# VestibularVR_H1-module_v1_0.net
KiCad netlist of a schematic drawn in EAGLE
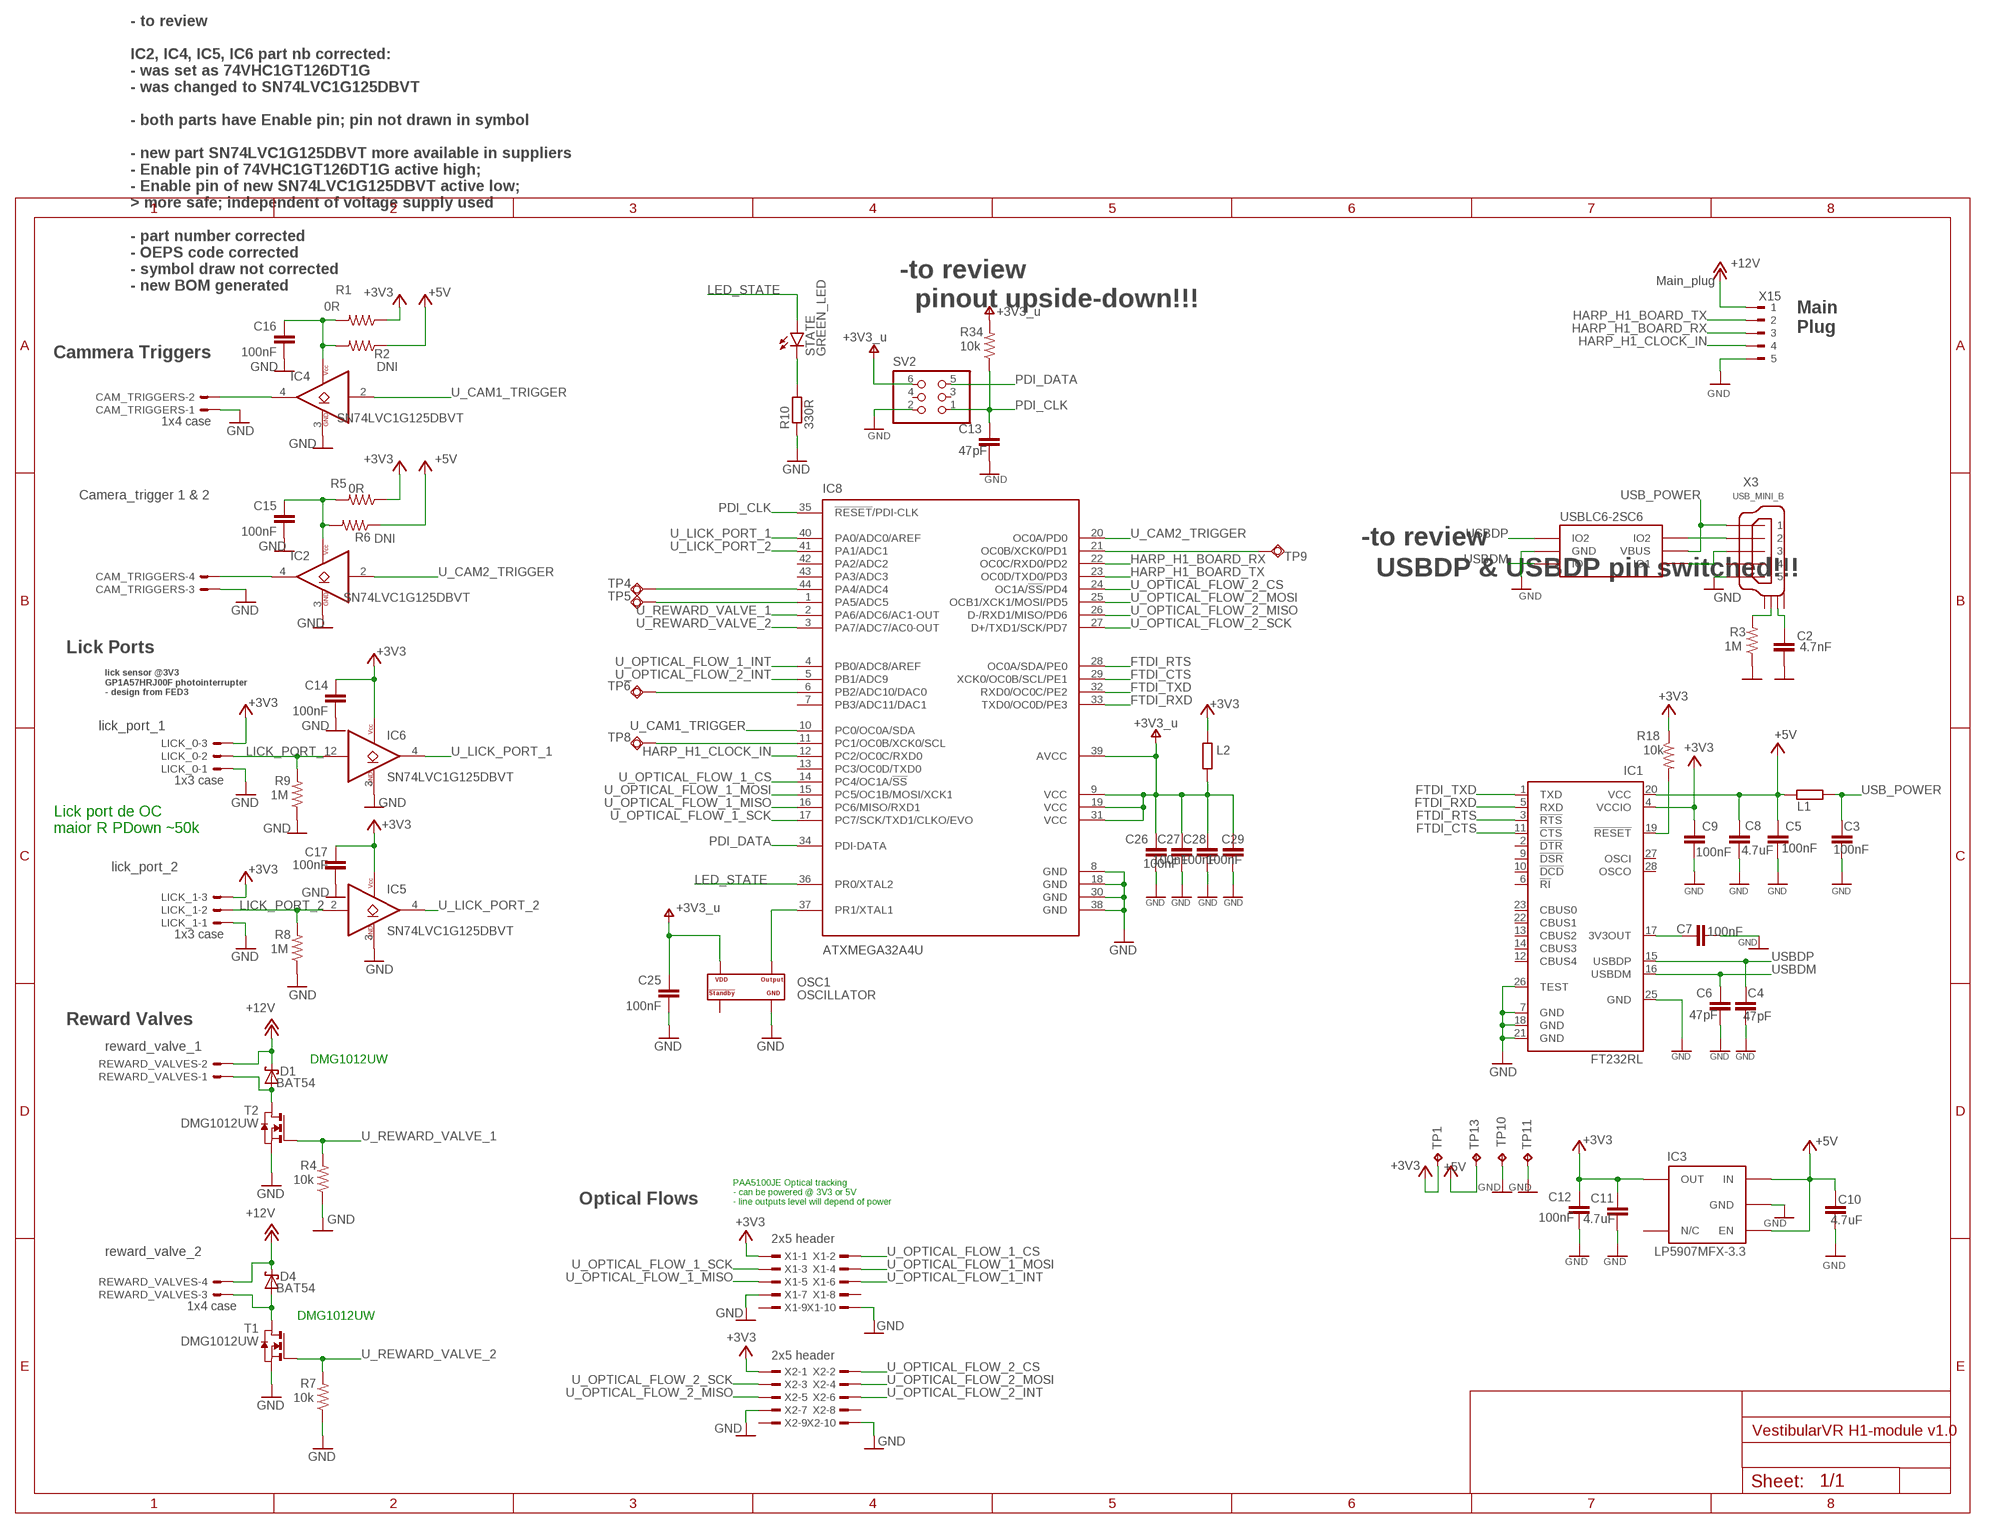
[diagram p0: schematic, sheet 1]

(export (version "E")
  (design (tool "Eeschema 10.0.6"))
  (components
    (comp (ref "C2")
      (value "4.7nF")
      (footprint "eagle-import:C0402K")
      (fields (field (name "MPN") "CC0402KRX7R8BB472"))
      (libsource (lib "eagle-import") (part "C-EUC0402K"))
    )
    (comp (ref "C3")
      (value "100nF")
      (footprint "eagle-import:C0402K")
      (fields (field (name "MPN") "C1005X7R1H104K050BB"))
      (libsource (lib "eagle-import") (part "C-EUC0402K"))
    )
    (comp (ref "C4")
      (value "47pF")
      (footprint "eagle-import:C0402K")
      (fields (field (name "MPN") "04025A470JAT2A"))
      (libsource (lib "eagle-import") (part "C-EUC0402K"))
    )
    (comp (ref "C5")
      (value "100nF")
      (footprint "eagle-import:C0402K")
      (fields (field (name "MPN") "C1005X7R1H104K050BB"))
      (libsource (lib "eagle-import") (part "C-EUC0402K"))
    )
    (comp (ref "C6")
      (value "47pF")
      (footprint "eagle-import:C0402K")
      (fields (field (name "MPN") "04025A470JAT2A"))
      (libsource (lib "eagle-import") (part "C-EUC0402K"))
    )
    (comp (ref "C7")
      (value "100nF")
      (footprint "eagle-import:C0402K")
      (fields (field (name "MPN") "C1005X7R1H104K050BB"))
      (libsource (lib "eagle-import") (part "C-EUC0402K"))
    )
    (comp (ref "C8")
      (value "4.7uF")
      (footprint "eagle-import:C0603")
      (fields (field (name "MPN") "C1608X6S1C475K080AC"))
      (libsource (lib "eagle-import") (part "C-EUC0603"))
    )
    (comp (ref "C9")
      (value "100nF")
      (footprint "eagle-import:C0402K")
      (fields (field (name "MPN") "C1005X7R1H104K050BB"))
      (libsource (lib "eagle-import") (part "C-EUC0402K"))
    )
    (comp (ref "C10")
      (value "4.7uF")
      (footprint "eagle-import:C0603K")
      (fields (field (name "MPN") "C1608X6S1C475K080AC"))
      (libsource (lib "eagle-import") (part "C-EUC0603K"))
    )
    (comp (ref "C11")
      (value "4.7uF")
      (footprint "eagle-import:C0603K")
      (fields (field (name "MPN") "C1608X6S1C475K080AC"))
      (libsource (lib "eagle-import") (part "C-EUC0603K"))
    )
    (comp (ref "C12")
      (value "100nF")
      (footprint "eagle-import:C0402K")
      (fields (field (name "MPN") "C1005X7R1H104K050BB"))
      (libsource (lib "eagle-import") (part "C-EUC0402K"))
    )
    (comp (ref "C13")
      (value "47pF")
      (footprint "eagle-import:C0402K")
      (fields (field (name "MPN") "04025A470JAT2A"))
      (libsource (lib "eagle-import") (part "C-EUC0402K"))
    )
    (comp (ref "C14")
      (value "100nF")
      (footprint "eagle-import:C0402K")
      (fields (field (name "MPN") "C1005X7R1H104K050BB"))
      (libsource (lib "eagle-import") (part "C-EUC0402K"))
    )
    (comp (ref "C15")
      (value "100nF")
      (footprint "eagle-import:C0402K")
      (fields (field (name "MPN") "C1005X7R1H104K050BB"))
      (libsource (lib "eagle-import") (part "C-EUC0402K"))
    )
    (comp (ref "C16")
      (value "100nF")
      (footprint "eagle-import:C0402K")
      (fields (field (name "MPN") "C1005X7R1H104K050BB"))
      (libsource (lib "eagle-import") (part "C-EUC0402K"))
    )
    (comp (ref "C17")
      (value "100nF")
      (footprint "eagle-import:C0402K")
      (fields (field (name "MPN") "C1005X7R1H104K050BB"))
      (libsource (lib "eagle-import") (part "C-EUC0402K"))
    )
    (comp (ref "C25")
      (value "100nF")
      (footprint "eagle-import:C0402K")
      (fields (field (name "MPN") "C1005X7R1H104K050BB"))
      (libsource (lib "eagle-import") (part "C-EUC0402K"))
    )
    (comp (ref "C26")
      (value "100nF")
      (footprint "eagle-import:C0402K")
      (fields (field (name "MPN") "C1005X7R1H104K050BB"))
      (libsource (lib "eagle-import") (part "C-EUC0402K"))
    )
    (comp (ref "C27")
      (value "100nF")
      (footprint "eagle-import:C0402K")
      (fields (field (name "MPN") "C1005X7R1H104K050BB"))
      (libsource (lib "eagle-import") (part "C-EUC0402K"))
    )
    (comp (ref "C28")
      (value "100nF")
      (footprint "eagle-import:C0402K")
      (fields (field (name "MPN") "C1005X7R1H104K050BB"))
      (libsource (lib "eagle-import") (part "C-EUC0402K"))
    )
    (comp (ref "C29")
      (value "100nF")
      (footprint "eagle-import:C0402K")
      (fields (field (name "MPN") "C1005X7R1H104K050BB"))
      (libsource (lib "eagle-import") (part "C-EUC0402K"))
    )
    (comp (ref "CAM_TRIGGERS")
      (value "1x4 case")
      (footprint "eagle-import:22-23-2041")
      (fields
        (field (name "MF") "MOLEX")
        (field (name "MPN") "22-23-2041")
        (field (name "MF_1") "-")
        (field (name "MPN_1") "282834-4")
        (field (name "OEPS") "OEPS070036")
      )
      (libsource (lib "eagle-import") (part "22-23-2041"))
    )
    (comp (ref "D1")
      (value "BAT54")
      (footprint "eagle-import:SOT23")
      (fields (field (name "MPN") "BAT54SLT1G"))
      (libsource (lib "eagle-import") (part "BAT54"))
    )
    (comp (ref "D4")
      (value "BAT54")
      (footprint "eagle-import:SOT23")
      (fields (field (name "MPN") "BAT54SLT1G"))
      (libsource (lib "eagle-import") (part "BAT54"))
    )
    (comp (ref "IC1")
      (value "FT232RL")
      (footprint "eagle-import:SSOP28")
      (libsource (lib "eagle-import") (part "FT232RL"))
    )
    (comp (ref "IC2")
      (value "SN74LVC1G125DBVT")
      (footprint "eagle-import:SOT23-5")
      (libsource (lib "eagle-import") (part "74LVC1G07DBV"))
    )
    (comp (ref "IC3")
      (value "LP5907MFX-3.3")
      (footprint "eagle-import:TSOT23-5")
      (fields (field (name "MPN") "LP5907MFX-3.3/NOPB"))
      (libsource (lib "eagle-import") (part "TLV700XX"))
    )
    (comp (ref "IC4")
      (value "SN74LVC1G125DBVT")
      (footprint "eagle-import:SOT23-5")
      (libsource (lib "eagle-import") (part "74LVC1G07DBV"))
    )
    (comp (ref "IC5")
      (value "SN74LVC1G125DBVT")
      (footprint "eagle-import:SOT23-5")
      (libsource (lib "eagle-import") (part "74LVC1G07DBV"))
    )
    (comp (ref "IC6")
      (value "SN74LVC1G125DBVT")
      (footprint "eagle-import:SOT23-5")
      (libsource (lib "eagle-import") (part "74LVC1G07DBV"))
    )
    (comp (ref "IC7")
      (value "USBLC6-2SC6")
      (footprint "eagle-import:SOT23-6L")
      (libsource (lib "eagle-import") (part "USBLC6-2SC6"))
    )
    (comp (ref "IC8")
      (value "ATXMEGA32A4U")
      (footprint "eagle-import:TQFP44")
      (fields (field (name "MPN") "ATXMEGA32A4U-AUR"))
      (libsource (lib "eagle-import") (part "XMEGA-A4_AT-XMEGA-XXA4-AUTQFP44"))
    )
    (comp (ref "L1")
      (value "40R@100MHz")
      (footprint "eagle-import:R0603")
      (fields (field (name "MPN") "MI0805K400R-10"))
      (libsource (lib "eagle-import") (part "R-EU_R0603"))
    )
    (comp (ref "L2")
      (value "40R@100MHz")
      (footprint "eagle-import:R0603")
      (fields (field (name "MPN") "MI0805K400R-10"))
      (libsource (lib "eagle-import") (part "R-EU_R0603"))
    )
    (comp (ref "LICK_0")
      (value "1x3 case")
      (footprint "eagle-import:22-23-2031")
      (fields
        (field (name "MF") "MOLEX")
        (field (name "MPN") "22-23-2031")
        (field (name "MF_1") "-")
        (field (name "MPN_1") "282834-3")
        (field (name "OEPS") "OEPS070035")
      )
      (libsource (lib "eagle-import") (part "22-23-2031"))
    )
    (comp (ref "LICK_1")
      (value "1x3 case")
      (footprint "eagle-import:22-23-2031")
      (fields
        (field (name "MF") "MOLEX")
        (field (name "MPN") "22-23-2031")
        (field (name "MF_1") "-")
        (field (name "MPN_1") "282834-3")
        (field (name "OEPS") "OEPS070035")
      )
      (libsource (lib "eagle-import") (part "22-23-2031"))
    )
    (comp (ref "OSC1")
      (value "OSCILLATOR")
      (footprint "eagle-import:OSCILLATOR_3.2X2.5")
      (fields (field (name "MPN") "DSC1001CI5-032.0000"))
      (libsource (lib "eagle-import") (part "OSCILLATOR"))
    )
    (comp (ref "R1")
      (value "0R")
      (footprint "eagle-import:R0402@1")
      (fields (field (name "MPN") "RC0402JR-070RL"))
      (libsource (lib "eagle-import") (part "R-US_R0402"))
    )
    (comp (ref "R2")
      (value "DNI")
      (footprint "eagle-import:R0402@1")
      (libsource (lib "eagle-import") (part "R-US_R0402"))
    )
    (comp (ref "R3")
      (value "1M")
      (footprint "eagle-import:R0402@1")
      (fields (field (name "MPN") "CRCW04021M00FKED"))
      (libsource (lib "eagle-import") (part "R-US_R0402"))
    )
    (comp (ref "R4")
      (value "10k")
      (footprint "eagle-import:R0402@1")
      (fields (field (name "MPN") "CRCW040210K0FKED"))
      (libsource (lib "eagle-import") (part "R-US_R0402"))
    )
    (comp (ref "R5")
      (value "0R")
      (footprint "eagle-import:R0402@1")
      (fields (field (name "MPN") "RC0402JR-070RL"))
      (libsource (lib "eagle-import") (part "R-US_R0402"))
    )
    (comp (ref "R6")
      (value "DNI")
      (footprint "eagle-import:R0402@1")
      (libsource (lib "eagle-import") (part "R-US_R0402"))
    )
    (comp (ref "R7")
      (value "10k")
      (footprint "eagle-import:R0402@1")
      (fields (field (name "MPN") "CRCW040210K0FKED"))
      (libsource (lib "eagle-import") (part "R-US_R0402"))
    )
    (comp (ref "R8")
      (value "1M")
      (footprint "eagle-import:R0402@1")
      (fields (field (name "MPN") "CRCW04021M00FKED"))
      (libsource (lib "eagle-import") (part "R-US_R0402"))
    )
    (comp (ref "R9")
      (value "1M")
      (footprint "eagle-import:R0402@1")
      (fields (field (name "MPN") "CRCW04021M00FKED"))
      (libsource (lib "eagle-import") (part "R-US_R0402"))
    )
    (comp (ref "R10")
      (value "330R")
      (footprint "eagle-import:R0402")
      (fields (field (name "MPN") "RC0402FR-07330RL"))
      (libsource (lib "eagle-import") (part "R-EU_R0402"))
    )
    (comp (ref "R18")
      (value "10k")
      (footprint "eagle-import:R0402@1")
      (fields (field (name "MPN") "CRCW040210K0FKED"))
      (libsource (lib "eagle-import") (part "R-US_R0402"))
    )
    (comp (ref "R34")
      (value "10k")
      (footprint "eagle-import:R0402@1")
      (fields (field (name "MPN") "CRCW040210K0FKED"))
      (libsource (lib "eagle-import") (part "R-US_R0402"))
    )
    (comp (ref "REWARD_VALVES")
      (value "1x4 case")
      (footprint "eagle-import:22-23-2041")
      (fields
        (field (name "MF") "MOLEX")
        (field (name "MPN") "22-23-2041")
        (field (name "MF_1") "-")
        (field (name "MPN_1") "282834-4")
        (field (name "OEPS") "OEPS070036")
      )
      (libsource (lib "eagle-import") (part "22-23-2041"))
    )
    (comp (ref "STATE")
      (value "GREEN_LED")
      (footprint "eagle-import:CHIP-LED0603")
      (fields (field (name "MPN") "LTST-C191KGKT"))
      (libsource (lib "eagle-import") (part "LEDCHIP-LED0603"))
    )
    (comp (ref "SV2")
      (value "PINHD-2X3")
      (footprint "eagle-import:2X03")
      (fields (field (name "MPN") "609-3210-ND"))
      (libsource (lib "eagle-import") (part "PINHD-2X3"))
    )
    (comp (ref "T1")
      (value "DMG1012UW")
      (footprint "eagle-import:SOT323")
      (fields (field (name "MPN") "DMG1012UW-7"))
      (libsource (lib "eagle-import") (part "DMG1012UW-7"))
    )
    (comp (ref "T2")
      (value "DMG1012UW")
      (footprint "eagle-import:SOT323")
      (fields (field (name "MPN") "DMG1012UW-7"))
      (libsource (lib "eagle-import") (part "DMG1012UW-7"))
    )
    (comp (ref "TP1")
      (value "NO_COMPONENT")
      (footprint "eagle-import:B1,27")
      (libsource (lib "eagle-import") (part "TPB1,27"))
    )
    (comp (ref "TP4")
      (value "NO_COMPONENT")
      (footprint "eagle-import:TP11R")
      (libsource (lib "eagle-import") (part "TPSQTP11R"))
    )
    (comp (ref "TP5")
      (value "NO_COMPONENT")
      (footprint "eagle-import:TP11R")
      (libsource (lib "eagle-import") (part "TPSQTP11R"))
    )
    (comp (ref "TP6")
      (value "NO_COMPONENT")
      (footprint "eagle-import:TP11R")
      (libsource (lib "eagle-import") (part "TPSQTP11R"))
    )
    (comp (ref "TP8")
      (value "NO_COMPONENT")
      (footprint "eagle-import:TP11R")
      (libsource (lib "eagle-import") (part "TPSQTP11R"))
    )
    (comp (ref "TP9")
      (value "NO_COMPONENT")
      (footprint "eagle-import:TP11R")
      (libsource (lib "eagle-import") (part "TPSQTP11R"))
    )
    (comp (ref "TP10")
      (value "NO_COMPONENT")
      (footprint "eagle-import:B1,27")
      (libsource (lib "eagle-import") (part "TPB1,27"))
    )
    (comp (ref "TP11")
      (value "NO_COMPONENT")
      (footprint "eagle-import:B1,27")
      (libsource (lib "eagle-import") (part "TPB1,27"))
    )
    (comp (ref "TP13")
      (value "NO_COMPONENT")
      (footprint "eagle-import:B1,27")
      (libsource (lib "eagle-import") (part "TPB1,27"))
    )
    (comp (ref "X1")
      (value "2x5 header")
      (footprint "eagle-import:TSW-105-02-S-D")
      (fields (field (name "OEPS") "n.a."))
      (libsource (lib "eagle-import") (part "TSW-105-02-S-D"))
    )
    (comp (ref "X2")
      (value "2x5 header")
      (footprint "eagle-import:TSW-105-02-S-D")
      (fields (field (name "MPN") "2x5 header") (field (name "OEPS") "n.a."))
      (libsource (lib "eagle-import") (part "TSW-105-02-S-D"))
    )
    (comp (ref "X3")
      (value "USB_MINI_B")
      (footprint "eagle-import:240-0002-1")
      (fields (field (name "MPN") "UX60-MB-5S8"))
      (libsource (lib "eagle-import") (part "USB_MINI_B"))
    )
    (comp (ref "X15")
      (value "Main_plug")
      (footprint "eagle-import:90G-5")
      (fields (field (name "MPN") "20.155MH/5-E"))
      (libsource (lib "eagle-import") (part "90G-5"))
    )
  )
  (nets
    (net (code "1") (name "+3V3") (class "Default")
      (node (ref "C11") (pin "1") (pinfunction "1_1") (pintype "passive"))
      (node (ref "C12") (pin "1") (pinfunction "1_1") (pintype "passive"))
      (node (ref "C14") (pin "1") (pinfunction "1_1") (pintype "passive"))
      (node (ref "C17") (pin "1") (pinfunction "1_1") (pintype "passive"))
      (node (ref "C9") (pin "1") (pinfunction "1_1") (pintype "passive"))
      (node (ref "IC1") (pin "4") (pinfunction "VCCIO_4") (pintype "power_in"))
      (node (ref "IC3") (pin "5") (pinfunction "OUT_5") (pintype "bidirectional"))
      (node (ref "IC5") (pin "5") (pinfunction "VCC_5") (pintype "bidirectional"))
      (node (ref "IC6") (pin "5") (pinfunction "VCC_5") (pintype "bidirectional"))
      (node (ref "L2") (pin "2") (pinfunction "2_2") (pintype "passive"))
      (node (ref "LICK_0") (pin "3") (pinfunction "S_3") (pintype "passive"))
      (node (ref "LICK_1") (pin "3") (pinfunction "S_3") (pintype "passive"))
      (node (ref "R1") (pin "1") (pinfunction "1_1") (pintype "passive"))
      (node (ref "R18") (pin "1") (pinfunction "1_1") (pintype "passive"))
      (node (ref "R5") (pin "1") (pinfunction "1_1") (pintype "passive"))
      (node (ref "TP1") (pin "TP") (pinfunction "TP_TP") (pintype "input"))
      (node (ref "X1") (pin "1") (pinfunction "1_1") (pintype "passive"))
      (node (ref "X2") (pin "1") (pinfunction "1_1") (pintype "passive"))
    )
    (net (code "2") (name "+3V3_u") (class "Default")
      (node (ref "C25") (pin "1") (pinfunction "1_1") (pintype "passive"))
      (node (ref "C26") (pin "1") (pinfunction "1_1") (pintype "passive"))
      (node (ref "C27") (pin "1") (pinfunction "1_1") (pintype "passive"))
      (node (ref "C28") (pin "1") (pinfunction "1_1") (pintype "passive"))
      (node (ref "C29") (pin "1") (pinfunction "1_1") (pintype "passive"))
      (node (ref "IC8") (pin "19") (pinfunction "VCC_19") (pintype "power_in"))
      (node (ref "IC8") (pin "31") (pinfunction "VCC_31") (pintype "power_in"))
      (node (ref "IC8") (pin "39") (pinfunction "AVCC_39") (pintype "power_in"))
      (node (ref "IC8") (pin "9") (pinfunction "VCC_9") (pintype "power_in"))
      (node (ref "L2") (pin "1") (pinfunction "1_1") (pintype "passive"))
      (node (ref "OSC1") (pin "P$4") (pinfunction "VDD_P$4") (pintype "passive"))
      (node (ref "R34") (pin "2") (pinfunction "2_2") (pintype "passive"))
      (node (ref "SV2") (pin "6") (pinfunction "6_6") (pintype "passive"))
    )
    (net (code "3") (name "+5V") (class "Default")
      (node (ref "C10") (pin "1") (pinfunction "1_1") (pintype "passive"))
      (node (ref "C5") (pin "1") (pinfunction "1_1") (pintype "passive"))
      (node (ref "C8") (pin "1") (pinfunction "1_1") (pintype "passive"))
      (node (ref "IC1") (pin "20") (pinfunction "VCC_20") (pintype "power_in"))
      (node (ref "IC3") (pin "1") (pinfunction "IN_1") (pintype "bidirectional"))
      (node (ref "IC3") (pin "3") (pinfunction "EN_3") (pintype "bidirectional"))
      (node (ref "L1") (pin "1") (pinfunction "1_1") (pintype "passive"))
      (node (ref "R2") (pin "1") (pinfunction "1_1") (pintype "passive"))
      (node (ref "R6") (pin "1") (pinfunction "1_1") (pintype "passive"))
      (node (ref "TP13") (pin "TP") (pinfunction "TP_TP") (pintype "input"))
    )
    (net (code "4") (name "+12V") (class "Default")
      (node (ref "D1") (pin "3") (pinfunction "C_3") (pintype "passive"))
      (node (ref "D4") (pin "3") (pinfunction "C_3") (pintype "passive"))
      (node (ref "REWARD_VALVES") (pin "2") (pinfunction "S_2") (pintype "passive"))
      (node (ref "REWARD_VALVES") (pin "4") (pinfunction "S_4") (pintype "passive"))
      (node (ref "X15") (pin "1") (pinfunction "1_1") (pintype "passive"))
    )
    (net (code "5") (name "/FTDI_CTS") (class "Default")
      (node (ref "IC1") (pin "11") (pinfunction "~{CTS}_11") (pintype "input"))
      (node (ref "IC8") (pin "29") (pinfunction "XCK0/OC0B/SCL/PE1_29") (pintype "bidirectional"))
    )
    (net (code "6") (name "/FTDI_RTS") (class "Default")
      (node (ref "IC1") (pin "3") (pinfunction "~{RTS}_3") (pintype "output"))
      (node (ref "IC8") (pin "28") (pinfunction "OC0A/SDA/PE0_28") (pintype "bidirectional"))
    )
    (net (code "7") (name "/FTDI_RXD") (class "Default")
      (node (ref "IC1") (pin "5") (pinfunction "RXD_5") (pintype "input"))
      (node (ref "IC8") (pin "33") (pinfunction "TXD0/OC0D/PE3_33") (pintype "bidirectional"))
    )
    (net (code "8") (name "/FTDI_TXD") (class "Default")
      (node (ref "IC1") (pin "1") (pinfunction "TXD_1") (pintype "output"))
      (node (ref "IC8") (pin "32") (pinfunction "RXD0/OC0C/PE2_32") (pintype "bidirectional"))
    )
    (net (code "9") (name "/HARP_H1_BOARD_RX") (class "Default")
      (node (ref "IC8") (pin "22") (pinfunction "OC0C/RXD0/PD2_22") (pintype "bidirectional"))
      (node (ref "X15") (pin "3") (pinfunction "3_3") (pintype "passive"))
    )
    (net (code "10") (name "/HARP_H1_BOARD_TX") (class "Default")
      (node (ref "IC8") (pin "23") (pinfunction "OC0D/TXD0/PD3_23") (pintype "bidirectional"))
      (node (ref "X15") (pin "2") (pinfunction "2_2") (pintype "passive"))
    )
    (net (code "11") (name "/HARP_H1_CLOCK_IN") (class "Default")
      (node (ref "IC8") (pin "12") (pinfunction "PC2/OC0C/RXD0_12") (pintype "bidirectional"))
      (node (ref "X15") (pin "4") (pinfunction "4_4") (pintype "passive"))
    )
    (net (code "12") (name "/LED_STATE") (class "Default")
      (node (ref "IC8") (pin "36") (pinfunction "PR0/XTAL2_36") (pintype "bidirectional"))
      (node (ref "STATE") (pin "A") (pinfunction "A_A") (pintype "passive"))
    )
    (net (code "13") (name "/LICK_PORT_1") (class "Default")
      (node (ref "IC6") (pin "2") (pinfunction "A_2") (pintype "bidirectional"))
      (node (ref "LICK_0") (pin "2") (pinfunction "S_2") (pintype "passive"))
      (node (ref "R9") (pin "2") (pinfunction "2_2") (pintype "passive"))
    )
    (net (code "14") (name "/LICK_PORT_2") (class "Default")
      (node (ref "IC5") (pin "2") (pinfunction "A_2") (pintype "bidirectional"))
      (node (ref "LICK_1") (pin "2") (pinfunction "S_2") (pintype "passive"))
      (node (ref "R8") (pin "2") (pinfunction "2_2") (pintype "passive"))
    )
    (net (code "15") (name "/PDI_CLK") (class "Default")
      (node (ref "C13") (pin "1") (pinfunction "1_1") (pintype "passive"))
      (node (ref "IC8") (pin "35") (pinfunction "~{RESET}/PDI-CLK_35") (pintype "input"))
      (node (ref "R34") (pin "1") (pinfunction "1_1") (pintype "passive"))
      (node (ref "SV2") (pin "1") (pinfunction "1_1") (pintype "passive"))
    )
    (net (code "16") (name "/PDI_DATA") (class "Default")
      (node (ref "IC8") (pin "34") (pinfunction "PDI-DATA_34") (pintype "bidirectional"))
      (node (ref "SV2") (pin "5") (pinfunction "5_5") (pintype "passive"))
    )
    (net (code "17") (name "/USBDM") (class "Default")
      (node (ref "C6") (pin "1") (pinfunction "1_1") (pintype "passive"))
      (node (ref "IC1") (pin "16") (pinfunction "USBDM_16") (pintype "bidirectional"))
      (node (ref "IC7") (pin "P$1") (pinfunction "IO1_P$1") (pintype "bidirectional"))
    )
    (net (code "18") (name "/USBDP") (class "Default")
      (node (ref "C4") (pin "1") (pinfunction "1_1") (pintype "passive"))
      (node (ref "IC1") (pin "15") (pinfunction "USBDP_15") (pintype "bidirectional"))
      (node (ref "IC7") (pin "P$3") (pinfunction "IO2_P$3") (pintype "bidirectional"))
    )
    (net (code "19") (name "/USB_POWER") (class "Default")
      (node (ref "C3") (pin "1") (pinfunction "1_1") (pintype "passive"))
      (node (ref "IC7") (pin "P$5") (pinfunction "VBUS_P$5") (pintype "bidirectional"))
      (node (ref "L1") (pin "2") (pinfunction "2_2") (pintype "passive"))
      (node (ref "X3") (pin "P$1") (pinfunction "1_P$1") (pintype "bidirectional"))
    )
    (net (code "20") (name "/U_CAM1_TRIGGER") (class "Default")
      (node (ref "IC4") (pin "2") (pinfunction "A_2") (pintype "bidirectional"))
      (node (ref "IC8") (pin "10") (pinfunction "PC0/OC0A/SDA_10") (pintype "bidirectional"))
    )
    (net (code "21") (name "/U_CAM2_TRIGGER") (class "Default")
      (node (ref "IC2") (pin "2") (pinfunction "A_2") (pintype "bidirectional"))
      (node (ref "IC8") (pin "20") (pinfunction "OC0A/PD0_20") (pintype "bidirectional"))
    )
    (net (code "22") (name "/U_LICK_PORT_1") (class "Default")
      (node (ref "IC6") (pin "4") (pinfunction "Y_4") (pintype "bidirectional"))
      (node (ref "IC8") (pin "40") (pinfunction "PA0/ADC0/AREF_40") (pintype "bidirectional"))
    )
    (net (code "23") (name "/U_LICK_PORT_2") (class "Default")
      (node (ref "IC5") (pin "4") (pinfunction "Y_4") (pintype "bidirectional"))
      (node (ref "IC8") (pin "41") (pinfunction "PA1/ADC1_41") (pintype "bidirectional"))
    )
    (net (code "24") (name "/U_OPTICAL_FLOW_1_CS") (class "Default")
      (node (ref "IC8") (pin "14") (pinfunction "PC4/OC1A/~{SS}_14") (pintype "bidirectional"))
      (node (ref "X1") (pin "2") (pinfunction "1_2") (pintype "passive"))
    )
    (net (code "25") (name "/U_OPTICAL_FLOW_1_INT") (class "Default")
      (node (ref "IC8") (pin "4") (pinfunction "PB0/ADC8/AREF_4") (pintype "bidirectional"))
      (node (ref "X1") (pin "6") (pinfunction "1_6") (pintype "passive"))
    )
    (net (code "26") (name "/U_OPTICAL_FLOW_1_MISO") (class "Default")
      (node (ref "IC8") (pin "16") (pinfunction "PC6/MISO/RXD1_16") (pintype "bidirectional"))
      (node (ref "X1") (pin "5") (pinfunction "1_5") (pintype "passive"))
    )
    (net (code "27") (name "/U_OPTICAL_FLOW_1_MOSI") (class "Default")
      (node (ref "IC8") (pin "15") (pinfunction "PC5/OC1B/MOSI/XCK1_15") (pintype "bidirectional"))
      (node (ref "X1") (pin "4") (pinfunction "1_4") (pintype "passive"))
    )
    (net (code "28") (name "/U_OPTICAL_FLOW_1_SCK") (class "Default")
      (node (ref "IC8") (pin "17") (pinfunction "PC7/SCK/TXD1/CLKO/EVO_17") (pintype "bidirectional"))
      (node (ref "X1") (pin "3") (pinfunction "1_3") (pintype "passive"))
    )
    (net (code "29") (name "/U_OPTICAL_FLOW_2_CS") (class "Default")
      (node (ref "IC8") (pin "24") (pinfunction "OC1A/~{SS}/PD4_24") (pintype "bidirectional"))
      (node (ref "X2") (pin "2") (pinfunction "1_2") (pintype "passive"))
    )
    (net (code "30") (name "/U_OPTICAL_FLOW_2_INT") (class "Default")
      (node (ref "IC8") (pin "5") (pinfunction "PB1/ADC9_5") (pintype "bidirectional"))
      (node (ref "X2") (pin "6") (pinfunction "1_6") (pintype "passive"))
    )
    (net (code "31") (name "/U_OPTICAL_FLOW_2_MISO") (class "Default")
      (node (ref "IC8") (pin "26") (pinfunction "D-/RXD1/MISO/PD6_26") (pintype "bidirectional"))
      (node (ref "X2") (pin "5") (pinfunction "1_5") (pintype "passive"))
    )
    (net (code "32") (name "/U_OPTICAL_FLOW_2_MOSI") (class "Default")
      (node (ref "IC8") (pin "25") (pinfunction "OCB1/XCK1/MOSI/PD5_25") (pintype "bidirectional"))
      (node (ref "X2") (pin "4") (pinfunction "1_4") (pintype "passive"))
    )
    (net (code "33") (name "/U_OPTICAL_FLOW_2_SCK") (class "Default")
      (node (ref "IC8") (pin "27") (pinfunction "D+/TXD1/SCK/PD7_27") (pintype "bidirectional"))
      (node (ref "X2") (pin "3") (pinfunction "1_3") (pintype "passive"))
    )
    (net (code "34") (name "/U_REWARD_VALVE_1") (class "Default")
      (node (ref "IC8") (pin "2") (pinfunction "PA6/ADC6/AC1-OUT_2") (pintype "bidirectional"))
      (node (ref "R4") (pin "2") (pinfunction "2_2") (pintype "passive"))
      (node (ref "T2") (pin "1") (pinfunction "G_1") (pintype "passive"))
    )
    (net (code "35") (name "/U_REWARD_VALVE_2") (class "Default")
      (node (ref "IC8") (pin "3") (pinfunction "PA7/ADC7/AC0-OUT_3") (pintype "bidirectional"))
      (node (ref "R7") (pin "2") (pinfunction "2_2") (pintype "passive"))
      (node (ref "T1") (pin "1") (pinfunction "G_1") (pintype "passive"))
    )
    (net (code "36") (name "GND") (class "Default")
      (node (ref "C10") (pin "2") (pinfunction "2_2") (pintype "passive"))
      (node (ref "C11") (pin "2") (pinfunction "2_2") (pintype "passive"))
      (node (ref "C12") (pin "2") (pinfunction "2_2") (pintype "passive"))
      (node (ref "C13") (pin "2") (pinfunction "2_2") (pintype "passive"))
      (node (ref "C14") (pin "2") (pinfunction "2_2") (pintype "passive"))
      (node (ref "C15") (pin "2") (pinfunction "2_2") (pintype "passive"))
      (node (ref "C16") (pin "2") (pinfunction "2_2") (pintype "passive"))
      (node (ref "C17") (pin "2") (pinfunction "2_2") (pintype "passive"))
      (node (ref "C2") (pin "2") (pinfunction "2_2") (pintype "passive"))
      (node (ref "C25") (pin "2") (pinfunction "2_2") (pintype "passive"))
      (node (ref "C26") (pin "2") (pinfunction "2_2") (pintype "passive"))
      (node (ref "C27") (pin "2") (pinfunction "2_2") (pintype "passive"))
      (node (ref "C28") (pin "2") (pinfunction "2_2") (pintype "passive"))
      (node (ref "C29") (pin "2") (pinfunction "2_2") (pintype "passive"))
      (node (ref "C3") (pin "2") (pinfunction "2_2") (pintype "passive"))
      (node (ref "C4") (pin "2") (pinfunction "2_2") (pintype "passive"))
      (node (ref "C5") (pin "2") (pinfunction "2_2") (pintype "passive"))
      (node (ref "C6") (pin "2") (pinfunction "2_2") (pintype "passive"))
      (node (ref "C7") (pin "2") (pinfunction "2_2") (pintype "passive"))
      (node (ref "C8") (pin "2") (pinfunction "2_2") (pintype "passive"))
      (node (ref "C9") (pin "2") (pinfunction "2_2") (pintype "passive"))
      (node (ref "CAM_TRIGGERS") (pin "1") (pinfunction "S_1") (pintype "passive"))
      (node (ref "CAM_TRIGGERS") (pin "3") (pinfunction "S_3") (pintype "passive"))
      (node (ref "IC1") (pin "18") (pinfunction "GND_18") (pintype "power_in"))
      (node (ref "IC1") (pin "21") (pinfunction "GND_21") (pintype "power_in"))
      (node (ref "IC1") (pin "25") (pinfunction "GND_25") (pintype "power_in"))
      (node (ref "IC1") (pin "26") (pinfunction "TEST_26") (pintype "input"))
      (node (ref "IC1") (pin "7") (pinfunction "GND_7") (pintype "power_in"))
      (node (ref "IC2") (pin "3") (pinfunction "GND_3") (pintype "bidirectional"))
      (node (ref "IC3") (pin "2") (pinfunction "GND_2") (pintype "bidirectional"))
      (node (ref "IC4") (pin "3") (pinfunction "GND_3") (pintype "bidirectional"))
      (node (ref "IC5") (pin "3") (pinfunction "GND_3") (pintype "bidirectional"))
      (node (ref "IC6") (pin "3") (pinfunction "GND_3") (pintype "bidirectional"))
      (node (ref "IC7") (pin "P$2") (pinfunction "GND_P$2") (pintype "bidirectional"))
      (node (ref "IC8") (pin "18") (pinfunction "GND_18") (pintype "power_in"))
      (node (ref "IC8") (pin "30") (pinfunction "GND_30") (pintype "power_in"))
      (node (ref "IC8") (pin "38") (pinfunction "GND_38") (pintype "power_in"))
      (node (ref "IC8") (pin "8") (pinfunction "GND_8") (pintype "power_in"))
      (node (ref "LICK_0") (pin "1") (pinfunction "S_1") (pintype "passive"))
      (node (ref "LICK_1") (pin "1") (pinfunction "S_1") (pintype "passive"))
      (node (ref "OSC1") (pin "P$2") (pinfunction "GND_P$2") (pintype "passive"))
      (node (ref "R10") (pin "1") (pinfunction "1_1") (pintype "passive"))
      (node (ref "R3") (pin "1") (pinfunction "1_1") (pintype "passive"))
      (node (ref "R4") (pin "1") (pinfunction "1_1") (pintype "passive"))
      (node (ref "R7") (pin "1") (pinfunction "1_1") (pintype "passive"))
      (node (ref "R8") (pin "1") (pinfunction "1_1") (pintype "passive"))
      (node (ref "R9") (pin "1") (pinfunction "1_1") (pintype "passive"))
      (node (ref "SV2") (pin "2") (pinfunction "2_2") (pintype "passive"))
      (node (ref "T1") (pin "2") (pinfunction "S_2") (pintype "passive"))
      (node (ref "T2") (pin "2") (pinfunction "S_2") (pintype "passive"))
      (node (ref "TP10") (pin "TP") (pinfunction "TP_TP") (pintype "input"))
      (node (ref "TP11") (pin "TP") (pinfunction "TP_TP") (pintype "input"))
      (node (ref "X1") (pin "10") (pinfunction "1_10") (pintype "passive"))
      (node (ref "X1") (pin "7") (pinfunction "1_7") (pintype "passive"))
      (node (ref "X15") (pin "5") (pinfunction "5_5") (pintype "passive"))
      (node (ref "X2") (pin "10") (pinfunction "1_10") (pintype "passive"))
      (node (ref "X2") (pin "7") (pinfunction "1_7") (pintype "passive"))
      (node (ref "X3") (pin "P$5") (pinfunction "5_P$5") (pintype "bidirectional"))
    )
    (net (code "37") (name "Net-(CAM_TRIGGERSB-S)") (class "Default")
      (node (ref "CAM_TRIGGERS") (pin "2") (pinfunction "S_2") (pintype "passive"))
      (node (ref "IC4") (pin "4") (pinfunction "Y_4") (pintype "bidirectional"))
    )
    (net (code "38") (name "Net-(CAM_TRIGGERSD-S)") (class "Default")
      (node (ref "CAM_TRIGGERS") (pin "4") (pinfunction "S_4") (pintype "passive"))
      (node (ref "IC2") (pin "4") (pinfunction "Y_4") (pintype "bidirectional"))
    )
    (net (code "39") (name "Net-(D1-A)") (class "Default")
      (node (ref "D1") (pin "1") (pinfunction "A_1") (pintype "passive"))
      (node (ref "REWARD_VALVES") (pin "1") (pinfunction "S_1") (pintype "passive"))
      (node (ref "T2") (pin "3") (pinfunction "D_3") (pintype "passive"))
    )
    (net (code "40") (name "Net-(D4-A)") (class "Default")
      (node (ref "D4") (pin "1") (pinfunction "A_1") (pintype "passive"))
      (node (ref "REWARD_VALVES") (pin "3") (pinfunction "S_3") (pintype "passive"))
      (node (ref "T1") (pin "3") (pinfunction "D_3") (pintype "passive"))
    )
    (net (code "41") (name "Net-(IC1-3V3OUT)") (class "Default")
      (node (ref "C7") (pin "1") (pinfunction "1_1") (pintype "passive"))
      (node (ref "IC1") (pin "17") (pinfunction "3V3OUT_17") (pintype "output"))
    )
    (net (code "42") (name "Net-(IC1-~{RESET})") (class "Default")
      (node (ref "IC1") (pin "19") (pinfunction "~{RESET}_19") (pintype "input"))
      (node (ref "R18") (pin "2") (pinfunction "2_2") (pintype "passive"))
    )
    (net (code "43") (name "Net-(IC2-VCC)") (class "Default")
      (node (ref "C15") (pin "1") (pinfunction "1_1") (pintype "passive"))
      (node (ref "IC2") (pin "5") (pinfunction "VCC_5") (pintype "bidirectional"))
      (node (ref "R5") (pin "2") (pinfunction "2_2") (pintype "passive"))
      (node (ref "R6") (pin "2") (pinfunction "2_2") (pintype "passive"))
    )
    (net (code "44") (name "Net-(IC4-VCC)") (class "Default")
      (node (ref "C16") (pin "1") (pinfunction "1_1") (pintype "passive"))
      (node (ref "IC4") (pin "5") (pinfunction "VCC_5") (pintype "bidirectional"))
      (node (ref "R1") (pin "2") (pinfunction "2_2") (pintype "passive"))
      (node (ref "R2") (pin "2") (pinfunction "2_2") (pintype "passive"))
    )
    (net (code "45") (name "Net-(IC8-OC0B{slash}XCK0{slash}PD1)") (class "Default")
      (node (ref "IC8") (pin "21") (pinfunction "OC0B/XCK0/PD1_21") (pintype "bidirectional"))
      (node (ref "TP9") (pin "TP") (pinfunction "TP_TP") (pintype "input"))
    )
    (net (code "46") (name "Net-(IC8-PA4{slash}ADC4)") (class "Default")
      (node (ref "IC8") (pin "44") (pinfunction "PA4/ADC4_44") (pintype "bidirectional"))
      (node (ref "TP4") (pin "TP") (pinfunction "TP_TP") (pintype "input"))
    )
    (net (code "47") (name "Net-(IC8-PA5{slash}ADC5)") (class "Default")
      (node (ref "IC8") (pin "1") (pinfunction "PA5/ADC5_1") (pintype "bidirectional"))
      (node (ref "TP5") (pin "TP") (pinfunction "TP_TP") (pintype "input"))
    )
    (net (code "48") (name "Net-(IC8-PB2{slash}ADC10{slash}DAC0)") (class "Default")
      (node (ref "IC8") (pin "6") (pinfunction "PB2/ADC10/DAC0_6") (pintype "bidirectional"))
      (node (ref "TP6") (pin "TP") (pinfunction "TP_TP") (pintype "input"))
    )
    (net (code "49") (name "Net-(IC8-PC1{slash}OC0B{slash}XCK0{slash}SCL)") (class "Default")
      (node (ref "IC8") (pin "11") (pinfunction "PC1/OC0B/XCK0/SCL_11") (pintype "bidirectional"))
      (node (ref "TP8") (pin "TP") (pinfunction "TP_TP") (pintype "input"))
    )
    (net (code "50") (name "Net-(IC8-PR1{slash}XTAL1)") (class "Default")
      (node (ref "IC8") (pin "37") (pinfunction "PR1/XTAL1_37") (pintype "bidirectional"))
      (node (ref "OSC1") (pin "P$3") (pinfunction "OUTPUT_P$3") (pintype "passive"))
    )
    (net (code "51") (name "Net-(R10-Pad2)") (class "Default")
      (node (ref "R10") (pin "2") (pinfunction "2_2") (pintype "passive"))
      (node (ref "STATE") (pin "C") (pinfunction "C_C") (pintype "passive"))
    )
    (net (code "52") (name "Net-(X3-2)") (class "Default")
      (node (ref "IC7") (pin "P$4") (pinfunction "IO2_P$4") (pintype "bidirectional"))
      (node (ref "X3") (pin "P$2") (pinfunction "2_P$2") (pintype "bidirectional"))
    )
    (net (code "53") (name "Net-(X3-3)") (class "Default")
      (node (ref "IC7") (pin "P$6") (pinfunction "IO1_P$6") (pintype "bidirectional"))
      (node (ref "X3") (pin "P$3") (pinfunction "3_P$3") (pintype "bidirectional"))
    )
    (net (code "54") (name "Net-(X3-P$2)") (class "Default")
      (node (ref "R3") (pin "2") (pinfunction "2_2") (pintype "passive"))
      (node (ref "X3") (pin "SHIELD_2") (pinfunction "P$2_SHIELD_2") (pintype "bidirectional"))
    )
    (net (code "55") (name "Net-(X3-P$3)") (class "Default")
      (node (ref "C2") (pin "1") (pinfunction "1_1") (pintype "passive"))
      (node (ref "X3") (pin "SHIELD_3") (pinfunction "P$3_SHIELD_3") (pintype "bidirectional"))
    )
    (net (code "56") (name "unconnected-(IC1-CBUS0-Pad23)") (class "Default")
      (node (ref "IC1") (pin "23") (pinfunction "CBUS0_23") (pintype "bidirectional"))
    )
    (net (code "57") (name "unconnected-(IC1-CBUS1-Pad22)") (class "Default")
      (node (ref "IC1") (pin "22") (pinfunction "CBUS1_22") (pintype "bidirectional"))
    )
    (net (code "58") (name "unconnected-(IC1-CBUS2-Pad13)") (class "Default")
      (node (ref "IC1") (pin "13") (pinfunction "CBUS2_13") (pintype "bidirectional"))
    )
    (net (code "59") (name "unconnected-(IC1-CBUS3-Pad14)") (class "Default")
      (node (ref "IC1") (pin "14") (pinfunction "CBUS3_14") (pintype "bidirectional"))
    )
    (net (code "60") (name "unconnected-(IC1-CBUS4-Pad12)") (class "Default")
      (node (ref "IC1") (pin "12") (pinfunction "CBUS4_12") (pintype "bidirectional"))
    )
    (net (code "61") (name "unconnected-(IC1-OSCI-Pad27)") (class "Default")
      (node (ref "IC1") (pin "27") (pinfunction "OSCI_27") (pintype "input"))
    )
    (net (code "62") (name "unconnected-(IC1-OSCO-Pad28)") (class "Default")
      (node (ref "IC1") (pin "28") (pinfunction "OSCO_28") (pintype "output"))
    )
    (net (code "63") (name "unconnected-(IC1-~{DCD}-Pad10)") (class "Default")
      (node (ref "IC1") (pin "10") (pinfunction "~{DCD}_10") (pintype "input"))
    )
    (net (code "64") (name "unconnected-(IC1-~{DSR}-Pad9)") (class "Default")
      (node (ref "IC1") (pin "9") (pinfunction "~{DSR}_9") (pintype "input"))
    )
    (net (code "65") (name "unconnected-(IC1-~{DTR}-Pad2)") (class "Default")
      (node (ref "IC1") (pin "2") (pinfunction "~{DTR}_2") (pintype "output"))
    )
    (net (code "66") (name "unconnected-(IC1-~{RI}-Pad6)") (class "Default")
      (node (ref "IC1") (pin "6") (pinfunction "~{RI}_6") (pintype "input"))
    )
    (net (code "67") (name "unconnected-(IC2-NC-Pad1)") (class "Default")
      (node (ref "IC2") (pin "1") (pinfunction "NC_1") (pintype "no_connect"))
    )
    (net (code "68") (name "unconnected-(IC3-N{slash}C-Pad4)") (class "Default")
      (node (ref "IC3") (pin "4") (pinfunction "N/C_4") (pintype "bidirectional"))
    )
    (net (code "69") (name "unconnected-(IC4-NC-Pad1)") (class "Default")
      (node (ref "IC4") (pin "1") (pinfunction "NC_1") (pintype "no_connect"))
    )
    (net (code "70") (name "unconnected-(IC5-NC-Pad1)") (class "Default")
      (node (ref "IC5") (pin "1") (pinfunction "NC_1") (pintype "no_connect"))
    )
    (net (code "71") (name "unconnected-(IC6-NC-Pad1)") (class "Default")
      (node (ref "IC6") (pin "1") (pinfunction "NC_1") (pintype "no_connect"))
    )
    (net (code "72") (name "unconnected-(IC8-PA2{slash}ADC2-Pad42)") (class "Default")
      (node (ref "IC8") (pin "42") (pinfunction "PA2/ADC2_42") (pintype "bidirectional"))
    )
    (net (code "73") (name "unconnected-(IC8-PA3{slash}ADC3-Pad43)") (class "Default")
      (node (ref "IC8") (pin "43") (pinfunction "PA3/ADC3_43") (pintype "bidirectional"))
    )
    (net (code "74") (name "unconnected-(IC8-PB3{slash}ADC11{slash}DAC1-Pad7)") (class "Default")
      (node (ref "IC8") (pin "7") (pinfunction "PB3/ADC11/DAC1_7") (pintype "bidirectional"))
    )
    (net (code "75") (name "unconnected-(IC8-PC3{slash}OC0D{slash}TXD0-Pad13)") (class "Default")
      (node (ref "IC8") (pin "13") (pinfunction "PC3/OC0D/TXD0_13") (pintype "bidirectional"))
    )
    (net (code "76") (name "unconnected-(OSC1-STANDBY#-PadP$1)") (class "Default")
      (node (ref "OSC1") (pin "P$1") (pinfunction "STANDBY#_P$1") (pintype "passive"))
    )
    (net (code "77") (name "unconnected-(SV2-Pad3)") (class "Default")
      (node (ref "SV2") (pin "3") (pinfunction "3_3") (pintype "passive"))
    )
    (net (code "78") (name "unconnected-(SV2-Pad4)") (class "Default")
      (node (ref "SV2") (pin "4") (pinfunction "4_4") (pintype "passive"))
    )
    (net (code "79") (name "unconnected-(X1I-1-Pad8)") (class "Default")
      (node (ref "X1") (pin "8") (pinfunction "1_8") (pintype "passive"))
    )
    (net (code "80") (name "unconnected-(X1J-1-Pad9)") (class "Default")
      (node (ref "X1") (pin "9") (pinfunction "1_9") (pintype "passive"))
    )
    (net (code "81") (name "unconnected-(X2I-1-Pad8)") (class "Default")
      (node (ref "X2") (pin "8") (pinfunction "1_8") (pintype "passive"))
    )
    (net (code "82") (name "unconnected-(X2J-1-Pad9)") (class "Default")
      (node (ref "X2") (pin "9") (pinfunction "1_9") (pintype "passive"))
    )
    (net (code "83") (name "unconnected-(X3-4-PadP$4)") (class "Default")
      (node (ref "X3") (pin "P$4") (pinfunction "4_P$4") (pintype "bidirectional"))
    )
    (net (code "84") (name "unconnected-(X3-P$1-PadSHIELD_1)") (class "Default")
      (node (ref "X3") (pin "SHIELD_1") (pinfunction "P$1_SHIELD_1") (pintype "bidirectional"))
    )
    (net (code "85") (name "unconnected-(X3-P$4-PadSHIELD_4)") (class "Default")
      (node (ref "X3") (pin "SHIELD_4") (pinfunction "P$4_SHIELD_4") (pintype "bidirectional"))
    )
  )
)
